# DMB.net
KiCad netlist of a schematic drawn in Altium Designer
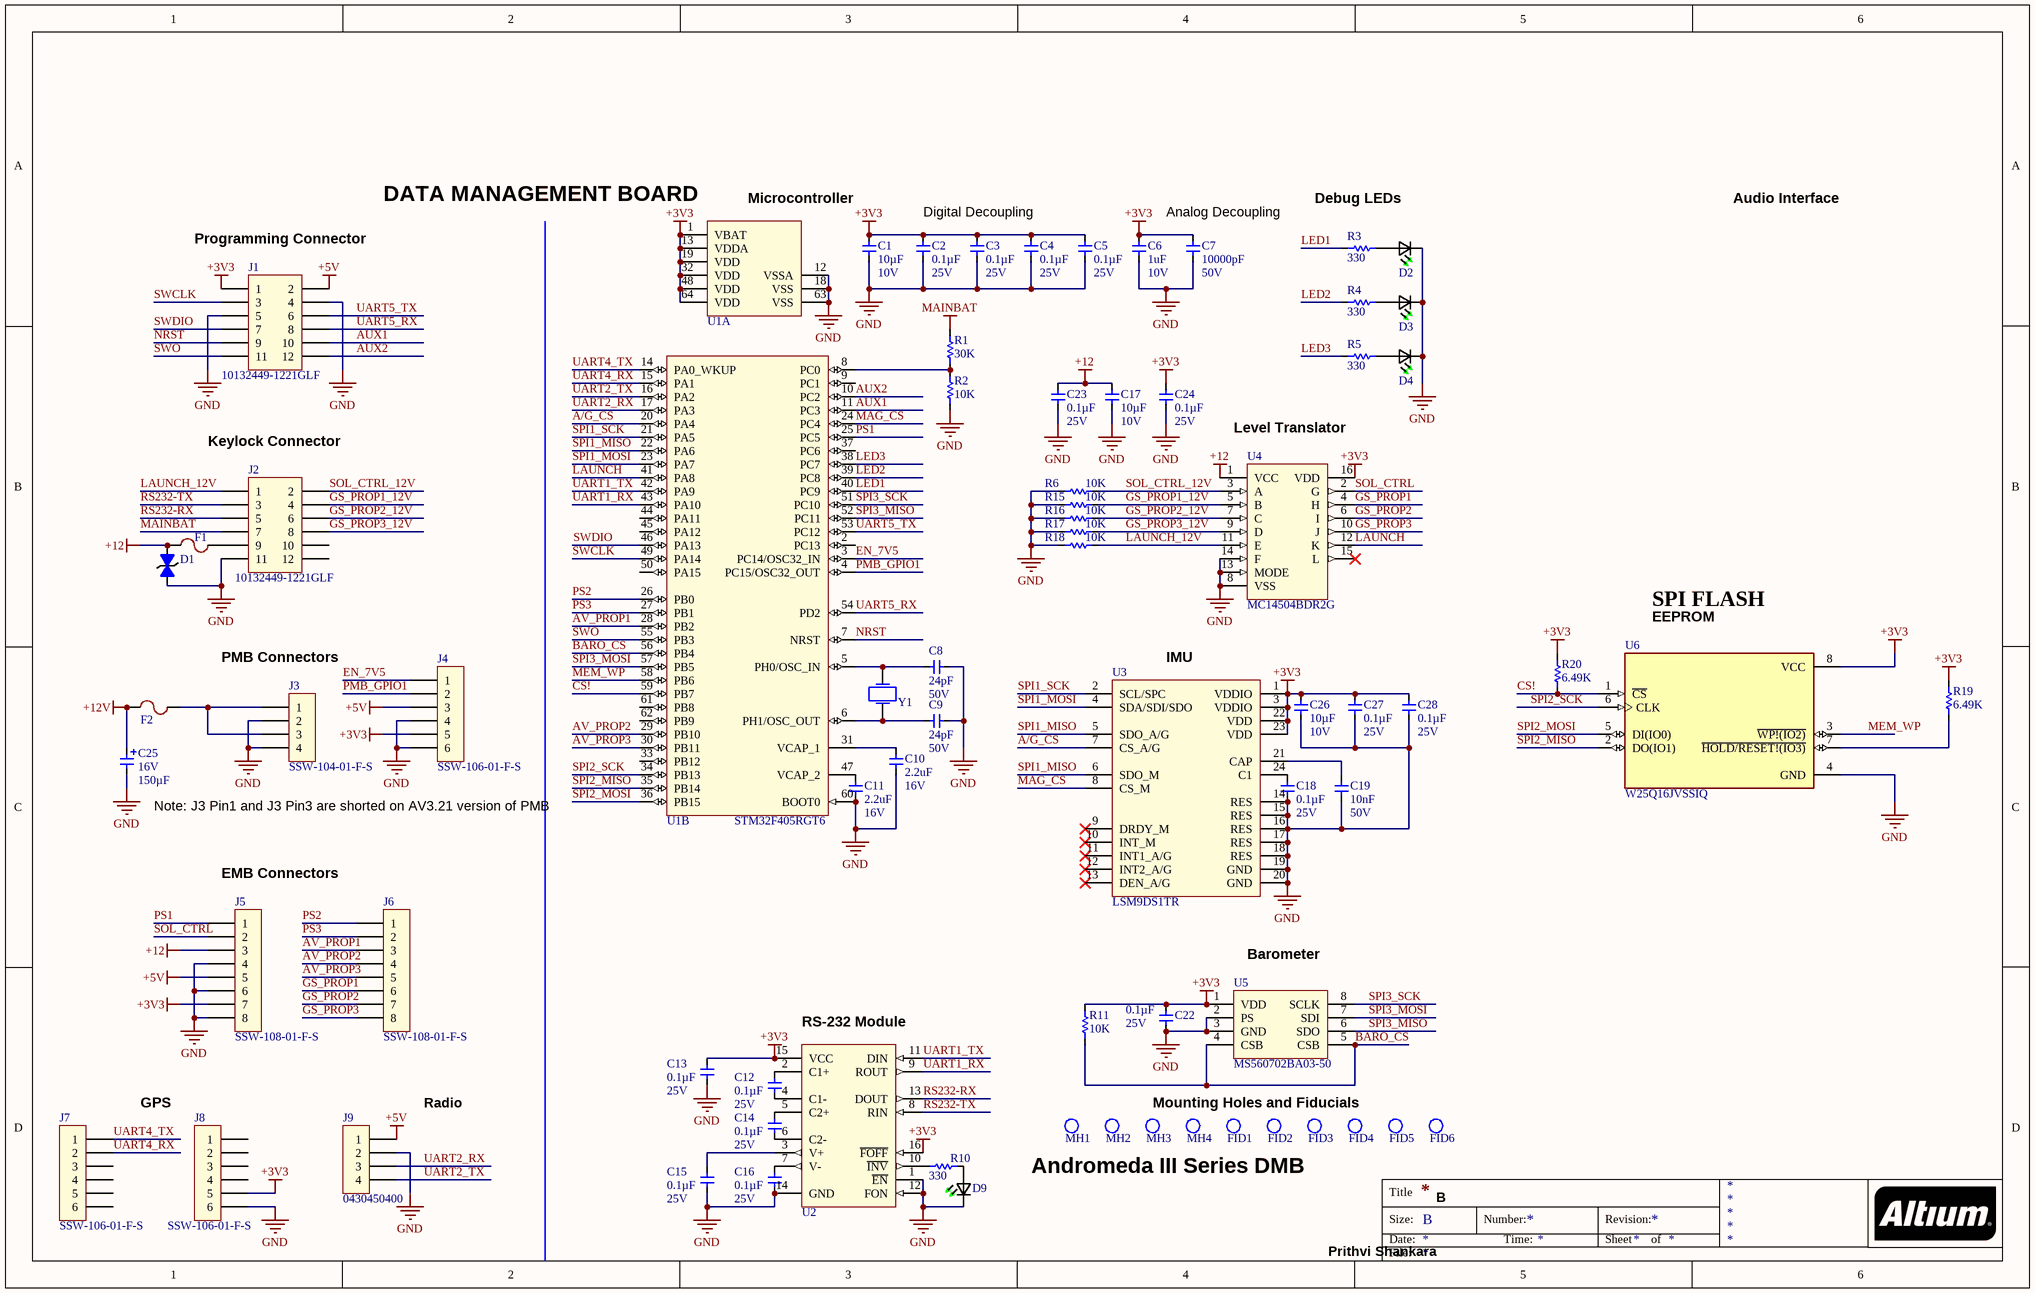
[diagram p0: DMB.SchDoc]

(export (version "E")
  (design (tool "Eeschema 10.0.6"))
  (components
    (comp (ref "C1")
      (value "CL10A106MP8NNNC")
      (footprint "0603[1608]")
      (description "CAP CER 10UF 10V X5R 0603")
      (fields
        (field (name "MANUFACTURER") "Samsung Electro-Mechanics")
        (field (name "TOLERANCE") "±20%")
        (field (name "CAPACITANCE") "10µF")
        (field (name "VOLTAGE - RATED") "10V")
      )
      (libsource (lib "SOARSchematics") (part "CL10A106MP8NNNC"))
    )
    (comp (ref "C2")
      (value "CGA3E2X7R1E104K080AA")
      (footprint "0603[1608]")
      (description "CAP CER 0.1UF 25V X7R 0603")
      (fields
        (field (name "MANUFACTURER") "TDK Corporation")
        (field (name "TOLERANCE") "±10%")
        (field (name "CAPACITANCE") "0.1µF")
        (field (name "VOLTAGE - RATED") "25V")
      )
      (libsource (lib "SOARSchematics") (part "CGA3E2X7R1E104K080AA"))
    )
    (comp (ref "C3")
      (value "CGA3E2X7R1E104K080AA")
      (footprint "0603[1608]")
      (description "CAP CER 0.1UF 25V X7R 0603")
      (fields
        (field (name "MANUFACTURER") "TDK Corporation")
        (field (name "TOLERANCE") "±10%")
        (field (name "CAPACITANCE") "0.1µF")
        (field (name "VOLTAGE - RATED") "25V")
      )
      (libsource (lib "SOARSchematics") (part "CGA3E2X7R1E104K080AA"))
    )
    (comp (ref "C4")
      (value "CGA3E2X7R1E104K080AA")
      (footprint "0603[1608]")
      (description "CAP CER 0.1UF 25V X7R 0603")
      (fields
        (field (name "MANUFACTURER") "TDK Corporation")
        (field (name "TOLERANCE") "±10%")
        (field (name "CAPACITANCE") "0.1µF")
        (field (name "VOLTAGE - RATED") "25V")
      )
      (libsource (lib "SOARSchematics") (part "CGA3E2X7R1E104K080AA"))
    )
    (comp (ref "C5")
      (value "CGA3E2X7R1E104K080AA")
      (footprint "0603[1608]")
      (description "CAP CER 0.1UF 25V X7R 0603")
      (fields
        (field (name "MANUFACTURER") "TDK Corporation")
        (field (name "TOLERANCE") "±10%")
        (field (name "CAPACITANCE") "0.1µF")
        (field (name "VOLTAGE - RATED") "25V")
      )
      (libsource (lib "SOARSchematics") (part "CGA3E2X7R1E104K080AA"))
    )
    (comp (ref "C6")
      (value "CL10A105KP8NNNC")
      (footprint "0603[1608]")
      (description "CAP CER 1UF 10V X5R 0603")
      (fields
        (field (name "MANUFACTURER") "Samsung Electro-Mechanics")
        (field (name "TOLERANCE") "±10%")
        (field (name "CAPACITANCE") "1uF")
        (field (name "VOLTAGE - RATED") "10V")
      )
      (libsource (lib "SOARSchematics") (part "CL10A105KP8NNNC"))
    )
    (comp (ref "C7")
      (value "CGA3E2X7R1H103K080AA")
      (footprint "0603[1608]")
      (description "CAP CER 10000PF 50V X7R 0603")
      (fields
        (field (name "MANUFACTURER") "TDK Corporation")
        (field (name "TOLERANCE") "±10%")
        (field (name "CAPACITANCE") "10000pF")
        (field (name "VOLTAGE - RATED") "50V")
      )
      (libsource (lib "SOARSchematics") (part "CGA3E2X7R1H103K080AA"))
    )
    (comp (ref "C8")
      (value "06035A240JAT2A")
      (footprint "0603[1608]")
      (description "CAP CER 24PF 50V NP0 0603")
      (fields
        (field (name "MANUFACTURER") "AVX Corporation")
        (field (name "TOLERANCE") "±5%")
        (field (name "CAPACITANCE") "24pF")
        (field (name "VOLTAGE - RATED") "50V")
      )
      (libsource (lib "SOARSchematics") (part "06035A240JAT2A"))
    )
    (comp (ref "C9")
      (value "06035A240JAT2A")
      (footprint "0603[1608]")
      (description "CAP CER 24PF 50V NP0 0603")
      (fields
        (field (name "MANUFACTURER") "AVX Corporation")
        (field (name "TOLERANCE") "±5%")
        (field (name "CAPACITANCE") "24pF")
        (field (name "VOLTAGE - RATED") "50V")
      )
      (libsource (lib "SOARSchematics") (part "06035A240JAT2A"))
    )
    (comp (ref "C10")
      (value "C1608X5R1C225K080AB")
      (footprint "0603[1608]")
      (description "CAP CER 2.2UF 16V X5R 0603")
      (fields
        (field (name "MANUFACTURER") "TDK Corporation")
        (field (name "TOLERANCE") "±10%")
        (field (name "CAPACITANCE") "2.2uF")
        (field (name "VOLTAGE - RATED") "16V")
      )
      (libsource (lib "SOARSchematics") (part "C1608X5R1C225K080AB"))
    )
    (comp (ref "C11")
      (value "C1608X5R1C225K080AB")
      (footprint "0603[1608]")
      (description "CAP CER 2.2UF 16V X5R 0603")
      (fields
        (field (name "MANUFACTURER") "TDK Corporation")
        (field (name "TOLERANCE") "±10%")
        (field (name "CAPACITANCE") "2.2uF")
        (field (name "VOLTAGE - RATED") "16V")
      )
      (libsource (lib "SOARSchematics") (part "C1608X5R1C225K080AB"))
    )
    (comp (ref "C12")
      (value "CGA3E2X7R1E104K080AA")
      (footprint "0603[1608]")
      (description "CAP CER 0.1UF 25V X7R 0603")
      (fields
        (field (name "MANUFACTURER") "TDK Corporation")
        (field (name "TOLERANCE") "±10%")
        (field (name "CAPACITANCE") "0.1µF")
        (field (name "VOLTAGE - RATED") "25V")
      )
      (libsource (lib "SOARSchematics") (part "CGA3E2X7R1E104K080AA"))
    )
    (comp (ref "C13")
      (value "CGA3E2X7R1E104K080AA")
      (footprint "0603[1608]")
      (description "CAP CER 0.1UF 25V X7R 0603")
      (fields
        (field (name "MANUFACTURER") "TDK Corporation")
        (field (name "TOLERANCE") "±10%")
        (field (name "CAPACITANCE") "0.1µF")
        (field (name "VOLTAGE - RATED") "25V")
      )
      (libsource (lib "SOARSchematics") (part "CGA3E2X7R1E104K080AA"))
    )
    (comp (ref "C14")
      (value "CGA3E2X7R1E104K080AA")
      (footprint "0603[1608]")
      (description "CAP CER 0.1UF 25V X7R 0603")
      (fields
        (field (name "MANUFACTURER") "TDK Corporation")
        (field (name "TOLERANCE") "±10%")
        (field (name "CAPACITANCE") "0.1µF")
        (field (name "VOLTAGE - RATED") "25V")
      )
      (libsource (lib "SOARSchematics") (part "CGA3E2X7R1E104K080AA"))
    )
    (comp (ref "C15")
      (value "CGA3E2X7R1E104K080AA")
      (footprint "0603[1608]")
      (description "CAP CER 0.1UF 25V X7R 0603")
      (fields
        (field (name "MANUFACTURER") "TDK Corporation")
        (field (name "TOLERANCE") "±10%")
        (field (name "CAPACITANCE") "0.1µF")
        (field (name "VOLTAGE - RATED") "25V")
      )
      (libsource (lib "SOARSchematics") (part "CGA3E2X7R1E104K080AA"))
    )
    (comp (ref "C16")
      (value "CGA3E2X7R1E104K080AA")
      (footprint "0603[1608]")
      (description "CAP CER 0.1UF 25V X7R 0603")
      (fields
        (field (name "MANUFACTURER") "TDK Corporation")
        (field (name "TOLERANCE") "±10%")
        (field (name "CAPACITANCE") "0.1µF")
        (field (name "VOLTAGE - RATED") "25V")
      )
      (libsource (lib "SOARSchematics") (part "CGA3E2X7R1E104K080AA"))
    )
    (comp (ref "C17")
      (value "CL10A106MP8NNNC")
      (footprint "0603[1608]")
      (description "CAP CER 10UF 10V X5R 0603")
      (fields
        (field (name "MANUFACTURER") "Samsung Electro-Mechanics")
        (field (name "TOLERANCE") "±20%")
        (field (name "CAPACITANCE") "10µF")
        (field (name "VOLTAGE - RATED") "10V")
      )
      (libsource (lib "SOARSchematics") (part "CL10A106MP8NNNC"))
    )
    (comp (ref "C18")
      (value "CGA3E2X7R1E104K080AA")
      (footprint "0603[1608]")
      (description "CAP CER 0.1UF 25V X7R 0603")
      (fields
        (field (name "MANUFACTURER") "TDK Corporation")
        (field (name "TOLERANCE") "±10%")
        (field (name "CAPACITANCE") "0.1µF")
        (field (name "VOLTAGE - RATED") "25V")
      )
      (libsource (lib "SOARSchematics") (part "CGA3E2X7R1E104K080AA"))
    )
    (comp (ref "C19")
      (value "GRM1885C1H103JA01D")
      (footprint "0603[1608]")
      (description "CAP CER 10000PF 50V C0G/NP0 0603")
      (fields
        (field (name "MANUFACTURER") "Murata Electronics")
        (field (name "TOLERANCE") "±50%")
        (field (name "CAPACITANCE") "10nF")
        (field (name "VOLTAGE - RATED") "50V")
      )
      (libsource (lib "SOARSchematics") (part "GRM1885C1H103JA01D"))
    )
    (comp (ref "C22")
      (value "CGA3E2X7R1E104K080AA")
      (footprint "0603[1608]")
      (description "CAP CER 0.1UF 25V X7R 0603")
      (fields
        (field (name "MANUFACTURER") "TDK Corporation")
        (field (name "TOLERANCE") "±10%")
        (field (name "CAPACITANCE") "0.1µF")
        (field (name "VOLTAGE - RATED") "25V")
      )
      (libsource (lib "SOARSchematics") (part "CGA3E2X7R1E104K080AA"))
    )
    (comp (ref "C23")
      (value "CGA3E2X7R1E104K080AA")
      (footprint "0603[1608]")
      (description "CAP CER 0.1UF 25V X7R 0603")
      (fields
        (field (name "MANUFACTURER") "TDK Corporation")
        (field (name "TOLERANCE") "±10%")
        (field (name "CAPACITANCE") "0.1µF")
        (field (name "VOLTAGE - RATED") "25V")
      )
      (libsource (lib "SOARSchematics") (part "CGA3E2X7R1E104K080AA"))
    )
    (comp (ref "C24")
      (value "CGA3E2X7R1E104K080AA")
      (footprint "0603[1608]")
      (description "CAP CER 0.1UF 25V X7R 0603")
      (fields
        (field (name "MANUFACTURER") "TDK Corporation")
        (field (name "TOLERANCE") "±10%")
        (field (name "CAPACITANCE") "0.1µF")
        (field (name "VOLTAGE - RATED") "25V")
      )
      (libsource (lib "SOARSchematics") (part "CGA3E2X7R1E104K080AA"))
    )
    (comp (ref "C25")
      (value "TAJD157K016RNJ")
      (footprint "TAJD157K016RNJ")
      (description "CAP TANT 150UF 10% 16V 2917")
      (fields
        (field (name "MANUFACTURER") "AVX Corporation")
        (field (name "TOLERANCE") "±10%")
        (field (name "VOLTAGE - RATED") "16V")
        (field (name "CAPACITANCE") "150µF")
      )
      (libsource (lib "SOARSchematics") (part "TAJD157K016RNJ"))
    )
    (comp (ref "C26")
      (value "CL10A106MP8NNNC")
      (footprint "0603[1608]")
      (description "CAP CER 10UF 10V X5R 0603")
      (fields
        (field (name "MANUFACTURER") "Samsung Electro-Mechanics")
        (field (name "TOLERANCE") "±20%")
        (field (name "CAPACITANCE") "10µF")
        (field (name "VOLTAGE - RATED") "10V")
      )
      (libsource (lib "SOARSchematics") (part "CL10A106MP8NNNC"))
    )
    (comp (ref "C27")
      (value "CGA3E2X7R1E104K080AA")
      (footprint "0603[1608]")
      (description "CAP CER 0.1UF 25V X7R 0603")
      (fields
        (field (name "MANUFACTURER") "TDK Corporation")
        (field (name "TOLERANCE") "±10%")
        (field (name "CAPACITANCE") "0.1µF")
        (field (name "VOLTAGE - RATED") "25V")
      )
      (libsource (lib "SOARSchematics") (part "CGA3E2X7R1E104K080AA"))
    )
    (comp (ref "C28")
      (value "CGA3E2X7R1E104K080AA")
      (footprint "0603[1608]")
      (description "CAP CER 0.1UF 25V X7R 0603")
      (fields
        (field (name "MANUFACTURER") "TDK Corporation")
        (field (name "TOLERANCE") "±10%")
        (field (name "CAPACITANCE") "0.1µF")
        (field (name "VOLTAGE - RATED") "25V")
      )
      (libsource (lib "SOARSchematics") (part "CGA3E2X7R1E104K080AA"))
    )
    (comp (ref "D1")
      (value "CDSOD323-T12C")
      (footprint "CDSOD323-T12C")
      (description "TVS DIODE 12V 28.3V SOD323")
      (fields (field (name "MANUFACTURER") "Bourns Inc."))
      (libsource (lib "SOARSchematics") (part "CDSOD323-T12C"))
    )
    (comp (ref "D2")
      (value "LTST-C191KGKT")
      (footprint "LTST-C191KGKT")
      (description "LED GREEN CLEAR SMD 0603")
      (fields (field (name "MANUFACTURER") "Lite-On Inc."))
      (libsource (lib "SOARSchematics") (part "LTST-C191KGKT"))
    )
    (comp (ref "D3")
      (value "LTST-C191KGKT")
      (footprint "LTST-C191KGKT")
      (description "LED GREEN CLEAR SMD 0603")
      (fields (field (name "MANUFACTURER") "Lite-On Inc."))
      (libsource (lib "SOARSchematics") (part "LTST-C191KGKT"))
    )
    (comp (ref "D4")
      (value "LTST-C191KGKT")
      (footprint "LTST-C191KGKT")
      (description "LED GREEN CLEAR SMD 0603")
      (fields (field (name "MANUFACTURER") "Lite-On Inc."))
      (libsource (lib "SOARSchematics") (part "LTST-C191KGKT"))
    )
    (comp (ref "D9")
      (value "LTST-C191KGKT")
      (footprint "LTST-C191KGKT")
      (description "LED GREEN CLEAR SMD 0603")
      (fields (field (name "MANUFACTURER") "Lite-On Inc."))
      (libsource (lib "SOARSchematics") (part "LTST-C191KGKT"))
    )
    (comp (ref "F1")
      (value "SF-0603FP500M-2")
      (footprint "SF-0603FP500M-2")
      (description "FUSE BOARD MOUNT 5A 32VDC 0603")
      (fields (field (name "MANUFACTURER") "Bourns Inc."))
      (libsource (lib "SOARSchematics") (part "SF-0603FP500M-2"))
    )
    (comp (ref "F2")
      (value "SF-0603FP500M-2")
      (footprint "SF-0603FP500M-2")
      (description "FUSE BOARD MOUNT 5A 32VDC 0603")
      (fields (field (name "MANUFACTURER") "Bourns Inc."))
      (libsource (lib "SOARSchematics") (part "SF-0603FP500M-2"))
    )
    (comp (ref "FID1")
      (value "FID_1MM_ROUND_SL")
      (footprint "FID_1MM_ROUND_SL")
      (description "Fiducial 1mm Round Single Layer")
      (libsource (lib "SOARSchematics") (part "FID_1MM_ROUND_SL"))
    )
    (comp (ref "FID2")
      (value "FID_1MM_ROUND_SL")
      (footprint "FID_1MM_ROUND_SL")
      (description "Fiducial 1mm Round Single Layer")
      (libsource (lib "SOARSchematics") (part "FID_1MM_ROUND_SL"))
    )
    (comp (ref "FID3")
      (value "FID_1MM_ROUND_SL")
      (footprint "FID_1MM_ROUND_SL")
      (description "Fiducial 1mm Round Single Layer")
      (libsource (lib "SOARSchematics") (part "FID_1MM_ROUND_SL"))
    )
    (comp (ref "FID4")
      (value "FID_1MM_ROUND_SL")
      (footprint "FID_1MM_ROUND_SL")
      (description "Fiducial 1mm Round Single Layer")
      (libsource (lib "SOARSchematics") (part "FID_1MM_ROUND_SL"))
    )
    (comp (ref "FID5")
      (value "FID_1MM_ROUND_SL")
      (footprint "FID_1MM_ROUND_SL")
      (description "Fiducial 1mm Round Single Layer")
      (libsource (lib "SOARSchematics") (part "FID_1MM_ROUND_SL"))
    )
    (comp (ref "FID6")
      (value "FID_1MM_ROUND_SL")
      (footprint "FID_1MM_ROUND_SL")
      (description "Fiducial 1mm Round Single Layer")
      (libsource (lib "SOARSchematics") (part "FID_1MM_ROUND_SL"))
    )
    (comp (ref "J1")
      (value "10132449-1221GLF")
      (footprint "10132449-1221GLF")
      (description "CONN HEADER R/A 12POS 3MM")
      (fields (field (name "MANUFACTURER") "Amphenol ICC (FCI)"))
      (libsource (lib "SOARSchematics") (part "10132449-1221GLF"))
    )
    (comp (ref "J2")
      (value "10132449-1221GLF")
      (footprint "10132449-1221GLF")
      (description "CONN HEADER R/A 12POS 3MM")
      (fields (field (name "MANUFACTURER") "Amphenol ICC (FCI)"))
      (libsource (lib "SOARSchematics") (part "10132449-1221GLF"))
    )
    (comp (ref "J3")
      (value "SSW-104-01-F-S")
      (footprint "SSW-104-01-F-S")
      (description "CONN RCPT 4POS FEMALE 0.1 GOLD PCB")
      (fields (field (name "MANUFACTURER") "Samtec Inc."))
      (libsource (lib "SOARSchematics") (part "SSW-104-01-F-S"))
    )
    (comp (ref "J4")
      (value "SSW-106-01-F-S")
      (footprint "SSW-106-01-F-S")
      (description "CONN RCPT 6POS FEMALE 0.1 GOLD PCB")
      (fields (field (name "MANUFACTURER") "Samtec Inc."))
      (libsource (lib "") (part "SSW-106-01-F-S_1"))
    )
    (comp (ref "J5")
      (value "SSW-108-01-F-S")
      (footprint "SSW-108-01-F-S")
      (description "CONN RCPT 8POS FEMALE 0.1 GOLD PCB")
      (fields (field (name "MANUFACTURER") "Samtec Inc."))
      (libsource (lib "SOARSchematics") (part "SSW-108-01-F-S"))
    )
    (comp (ref "J6")
      (value "SSW-108-01-F-S")
      (footprint "SSW-108-01-F-S")
      (description "CONN RCPT 8POS FEMALE 0.1 GOLD PCB")
      (fields (field (name "MANUFACTURER") "Samtec Inc."))
      (libsource (lib "SOARSchematics") (part "SSW-108-01-F-S"))
    )
    (comp (ref "J7")
      (value "SSW-106-01-F-S")
      (footprint "SSW-106-01-F-S")
      (description "CONN RCPT 6POS FEMALE 0.1 GOLD PCB")
      (fields (field (name "MANUFACTURER") "Samtec Inc."))
      (libsource (lib "SOARSchematics") (part "SSW-106-01-F-S"))
    )
    (comp (ref "J8")
      (value "SSW-106-01-F-S")
      (footprint "SSW-106-01-F-S")
      (description "CONN RCPT 6POS FEMALE 0.1 GOLD PCB")
      (fields (field (name "MANUFACTURER") "Samtec Inc."))
      (libsource (lib "SOARSchematics") (part "SSW-106-01-F-S"))
    )
    (comp (ref "J9")
      (value "0430450400")
      (footprint "0430450400")
      (description "CONN HEADER R/A 4POS 3MM")
      (fields (field (name "MANUFACTURER") "Molex"))
      (libsource (lib "SOARSchematics") (part "0430450400"))
    )
    (comp (ref "MH1")
      (value "Mounting Hole")
      (footprint "MOUNT-HOLE")
      (description "#4 Screw, 0.116in Diameter")
      (libsource (lib "SOARSchematics") (part "Mounting Hole"))
    )
    (comp (ref "MH2")
      (value "Mounting Hole")
      (footprint "MOUNT-HOLE")
      (description "#4 Screw, 0.116in Diameter")
      (libsource (lib "SOARSchematics") (part "Mounting Hole"))
    )
    (comp (ref "MH3")
      (value "Mounting Hole")
      (footprint "MOUNT-HOLE")
      (description "#4 Screw, 0.116in Diameter")
      (libsource (lib "SOARSchematics") (part "Mounting Hole"))
    )
    (comp (ref "MH4")
      (value "Mounting Hole")
      (footprint "MOUNT-HOLE")
      (description "#4 Screw, 0.116in Diameter")
      (libsource (lib "SOARSchematics") (part "Mounting Hole"))
    )
    (comp (ref "R1")
      (value "RC0603FR-0730KL")
      (footprint "0603[1608]")
      (description "RES SMD 30K OHM 1% 1/10W 0603")
      (fields
        (field (name "TOLERANCE") "±1%")
        (field (name "MANUFACTURER") "Yageo")
        (field (name "RESISTANCE") "30K")
      )
      (libsource (lib "SOARSchematics") (part "RC0603FR-0730KL"))
    )
    (comp (ref "R2")
      (value "ERJ-3GEYJ103V")
      (footprint "0603[1608]")
      (description "RES SMD 10K OHM 5% 1/10W 0603")
      (fields
        (field (name "TOLERANCE") "±5%")
        (field (name "MANUFACTURER") "Panasonic Electronic Components")
        (field (name "RESISTANCE") "10K")
      )
      (libsource (lib "SOARSchematics") (part "ERJ-3GEYJ103V"))
    )
    (comp (ref "R3")
      (value "RC1608F331CS")
      (footprint "0603[1608]")
      (description "RES SMD 330 OHM 1% 1/10W 0603")
      (fields
        (field (name "TOLERANCE") "±1%")
        (field (name "MANUFACTURER") "Samsung Electro-Mechanics")
        (field (name "RESISTANCE") "330")
      )
      (libsource (lib "SOARSchematics") (part "RC1608F331CS"))
    )
    (comp (ref "R4")
      (value "RC1608F331CS")
      (footprint "0603[1608]")
      (description "RES SMD 330 OHM 1% 1/10W 0603")
      (fields
        (field (name "TOLERANCE") "±1%")
        (field (name "MANUFACTURER") "Samsung Electro-Mechanics")
        (field (name "RESISTANCE") "330")
      )
      (libsource (lib "SOARSchematics") (part "RC1608F331CS"))
    )
    (comp (ref "R5")
      (value "RC1608F331CS")
      (footprint "0603[1608]")
      (description "RES SMD 330 OHM 1% 1/10W 0603")
      (fields
        (field (name "TOLERANCE") "±1%")
        (field (name "MANUFACTURER") "Samsung Electro-Mechanics")
        (field (name "RESISTANCE") "330")
      )
      (libsource (lib "SOARSchematics") (part "RC1608F331CS"))
    )
    (comp (ref "R6")
      (value "ERJ-3GEYJ103V")
      (footprint "0603[1608]")
      (description "RES SMD 10K OHM 5% 1/10W 0603")
      (fields
        (field (name "TOLERANCE") "±5%")
        (field (name "MANUFACTURER") "Panasonic Electronic Components")
        (field (name "RESISTANCE") "10K")
      )
      (libsource (lib "SOARSchematics") (part "ERJ-3GEYJ103V"))
    )
    (comp (ref "R10")
      (value "RC1608F331CS")
      (footprint "0603[1608]")
      (description "RES SMD 330 OHM 1% 1/10W 0603")
      (fields
        (field (name "TOLERANCE") "±1%")
        (field (name "MANUFACTURER") "Samsung Electro-Mechanics")
        (field (name "RESISTANCE") "330")
      )
      (libsource (lib "SOARSchematics") (part "RC1608F331CS"))
    )
    (comp (ref "R11")
      (value "ERJ-3GEYJ103V")
      (footprint "0603[1608]")
      (description "RES SMD 10K OHM 5% 1/10W 0603")
      (fields
        (field (name "TOLERANCE") "±5%")
        (field (name "MANUFACTURER") "Panasonic Electronic Components")
        (field (name "RESISTANCE") "10K")
      )
      (libsource (lib "SOARSchematics") (part "ERJ-3GEYJ103V"))
    )
    (comp (ref "R15")
      (value "ERJ-3GEYJ103V")
      (footprint "0603[1608]")
      (description "RES SMD 10K OHM 5% 1/10W 0603")
      (fields
        (field (name "TOLERANCE") "±5%")
        (field (name "MANUFACTURER") "Panasonic Electronic Components")
        (field (name "RESISTANCE") "10K")
      )
      (libsource (lib "SOARSchematics") (part "ERJ-3GEYJ103V"))
    )
    (comp (ref "R16")
      (value "ERJ-3GEYJ103V")
      (footprint "0603[1608]")
      (description "RES SMD 10K OHM 5% 1/10W 0603")
      (fields
        (field (name "TOLERANCE") "±5%")
        (field (name "MANUFACTURER") "Panasonic Electronic Components")
        (field (name "RESISTANCE") "10K")
      )
      (libsource (lib "SOARSchematics") (part "ERJ-3GEYJ103V"))
    )
    (comp (ref "R17")
      (value "ERJ-3GEYJ103V")
      (footprint "0603[1608]")
      (description "RES SMD 10K OHM 5% 1/10W 0603")
      (fields
        (field (name "TOLERANCE") "±5%")
        (field (name "MANUFACTURER") "Panasonic Electronic Components")
        (field (name "RESISTANCE") "10K")
      )
      (libsource (lib "SOARSchematics") (part "ERJ-3GEYJ103V"))
    )
    (comp (ref "R18")
      (value "ERJ-3GEYJ103V")
      (footprint "0603[1608]")
      (description "RES SMD 10K OHM 5% 1/10W 0603")
      (fields
        (field (name "TOLERANCE") "±5%")
        (field (name "MANUFACTURER") "Panasonic Electronic Components")
        (field (name "RESISTANCE") "10K")
      )
      (libsource (lib "SOARSchematics") (part "ERJ-3GEYJ103V"))
    )
    (comp (ref "R19")
      (value "RT0603DRE076K49L")
      (footprint "0603[1608]")
      (description "RES SMD 6.49KOHM 0.5% 1/10W 0603")
      (fields
        (field (name "TOLERANCE") "±0.5%")
        (field (name "MANUFACTURER") "Yageo")
        (field (name "RESISTANCE") "6.49K")
      )
      (libsource (lib "SOARSchematics") (part "RT0603DRE076K49L"))
    )
    (comp (ref "R20")
      (value "RT0603DRE076K49L")
      (footprint "0603[1608]")
      (description "RES SMD 6.49KOHM 0.5% 1/10W 0603")
      (fields
        (field (name "TOLERANCE") "±0.5%")
        (field (name "MANUFACTURER") "Yageo")
        (field (name "RESISTANCE") "6.49K")
      )
      (libsource (lib "SOARSchematics") (part "RT0603DRE076K49L"))
    )
    (comp (ref "U1")
      (value "STM32F405RGT6")
      (footprint "TSQFP50P1200X1200X160-64N")
      (description "IC MCU 32BIT 1MB FLASH 64LQFP")
      (fields (field (name "MANUFACTURER") "STMicroelectronics"))
      (libsource (lib "SOARSchematics") (part "STM32F405RGT6"))
    )
    (comp (ref "U2")
      (value "MAX3221ECPWR")
      (footprint "SOP65P780X200-16N")
      (description "IC TRANSCEIVER FULL 1/1 16TSSOP")
      (fields (field (name "MANUFACTURER") "Texas Instruments") (field (name "BASE PART NUMBER") "MAX3221E"))
      (libsource (lib "SOARSchematics") (part "MAX3221ECPWR"))
    )
    (comp (ref "U3")
      (value "LSM9DS1TR")
      (footprint "LSM9DS1TR")
      (description "IMU ACCEL/GYRO/MAG I2C/SPI 24LGA")
      (fields (field (name "MANUFACTURER") "STMicroelectronics"))
      (libsource (lib "SOARSchematics") (part "LSM9DS1TR"))
    )
    (comp (ref "U4")
      (value "MC14504BDR2G")
      (footprint "MC14504BDR2G")
      (description "IC TRNSLTR UNIDIRECTIONAL 16SOIC")
      (fields (field (name "MANUFACTURER") "ON Semiconductor"))
      (libsource (lib "SOARSchematics") (part "MC14504BDR2G"))
    )
    (comp (ref "U5")
      (value "MS560702BA03-50")
      (footprint "MS560702BA03-50")
      (description "BAROMETRIC PRESSURE SENSOR")
      (fields
        (field (name "DIGI-KEY PART NUMBER") "223-1198-1-ND")
        (field (name "MANUFACTURER") "TE Connectivity Measurement Specialties")
      )
      (libsource (lib "SOARSchematics") (part "MS560702BA03-50"))
    )
    (comp (ref "U6")
      (value "W25Q16JVSSIQ")
      (footprint "W25Q16JVSSIQ")
      (description "FLASH - NOR Memory IC 16Mb _2M x 8_ SPI - Quad I/O 133MHz 8-SOIC")
      (fields (field (name "MF") "Winbond Electronics"))
      (libsource (lib "SOARSchematics") (part "W25Q16JVSSIQ"))
    )
    (comp (ref "Y1")
      (value "ABLS-8.000MHZ-B2-T")
      (footprint "ABLS-8.000MHZ-B2-T")
      (description "CRYSTAL 8.0000MHZ 18PF SMD")
      (fields (field (name "MANUFACTURER") "Abracon LLC"))
      (libsource (lib "SOARSchematics") (part "ABLS-8.000MHZ-B2-T"))
    )
  )
  (nets
    (net (code "1") (name "+3V3") (class "Default")
      (node (ref "C1") (pin "2") (pinfunction "2_2") (pintype "passive"))
      (node (ref "C13") (pin "2") (pinfunction "2_2") (pintype "passive"))
      (node (ref "C2") (pin "2") (pinfunction "2_2") (pintype "passive"))
      (node (ref "C22") (pin "2") (pinfunction "2_2") (pintype "passive"))
      (node (ref "C24") (pin "2") (pinfunction "2_2") (pintype "passive"))
      (node (ref "C26") (pin "2") (pinfunction "2_2") (pintype "passive"))
      (node (ref "C27") (pin "2") (pinfunction "2_2") (pintype "passive"))
      (node (ref "C28") (pin "2") (pinfunction "2_2") (pintype "passive"))
      (node (ref "C3") (pin "2") (pinfunction "2_2") (pintype "passive"))
      (node (ref "C4") (pin "2") (pinfunction "2_2") (pintype "passive"))
      (node (ref "C5") (pin "2") (pinfunction "2_2") (pintype "passive"))
      (node (ref "C6") (pin "2") (pinfunction "2_2") (pintype "passive"))
      (node (ref "C7") (pin "2") (pinfunction "2_2") (pintype "passive"))
      (node (ref "J1") (pin "1") (pinfunction "1_1") (pintype "passive"))
      (node (ref "J4") (pin "5") (pinfunction "5_5") (pintype "passive"))
      (node (ref "J5") (pin "7") (pinfunction "7_7") (pintype "passive"))
      (node (ref "J8") (pin "5") (pinfunction "5_5") (pintype "passive"))
      (node (ref "R11") (pin "2") (pinfunction "2_2") (pintype "passive"))
      (node (ref "R19") (pin "2") (pinfunction "2_2") (pintype "passive"))
      (node (ref "R20") (pin "2") (pinfunction "2_2") (pintype "passive"))
      (node (ref "U1") (pin "1") (pinfunction "VBAT_1") (pintype "power_in"))
      (node (ref "U1") (pin "13") (pinfunction "VDDA_13") (pintype "power_in"))
      (node (ref "U1") (pin "19") (pinfunction "VDD_19") (pintype "power_in"))
      (node (ref "U1") (pin "32") (pinfunction "VDD_32") (pintype "power_in"))
      (node (ref "U1") (pin "48") (pinfunction "VDD_48") (pintype "power_in"))
      (node (ref "U1") (pin "64") (pinfunction "VDD_64") (pintype "power_in"))
      (node (ref "U2") (pin "15") (pinfunction "VCC_15") (pintype "passive"))
      (node (ref "U2") (pin "16") (pinfunction "~{FOFF}_16") (pintype "input"))
      (node (ref "U3") (pin "1") (pinfunction "VDDIO_1") (pintype "power_in"))
      (node (ref "U3") (pin "22") (pinfunction "VDD_22") (pintype "power_in"))
      (node (ref "U3") (pin "23") (pinfunction "VDD_23") (pintype "power_in"))
      (node (ref "U3") (pin "3") (pinfunction "VDDIO_3") (pintype "power_in"))
      (node (ref "U4") (pin "16") (pinfunction "VDD_16") (pintype "power_in"))
      (node (ref "U5") (pin "1") (pinfunction "VDD_1") (pintype "power_in"))
      (node (ref "U6") (pin "8") (pinfunction "VCC_8") (pintype "power_in"))
    )
    (net (code "2") (name "+5V") (class "Default")
      (node (ref "J1") (pin "2") (pinfunction "2_2") (pintype "passive"))
      (node (ref "J4") (pin "3") (pinfunction "3_3") (pintype "passive"))
      (node (ref "J5") (pin "5") (pinfunction "5_5") (pintype "passive"))
      (node (ref "J9") (pin "1") (pinfunction "1_1") (pintype "passive"))
    )
    (net (code "3") (name "+12") (class "Default")
      (node (ref "C17") (pin "2") (pinfunction "2_2") (pintype "passive"))
      (node (ref "C23") (pin "2") (pinfunction "2_2") (pintype "passive"))
      (node (ref "D1") (pin "1") (pinfunction "1_1") (pintype "power_in"))
      (node (ref "F1") (pin "1") (pinfunction "1_1") (pintype "passive"))
      (node (ref "J5") (pin "3") (pinfunction "3_3") (pintype "passive"))
      (node (ref "U4") (pin "1") (pinfunction "VCC_1") (pintype "power_in"))
    )
    (net (code "4") (name "+12V") (class "Default")
      (node (ref "C25") (pin "1") (pinfunction "1_1") (pintype "passive"))
      (node (ref "F2") (pin "1") (pinfunction "1_1") (pintype "passive"))
    )
    (net (code "6") (name "/AUX1") (class "Default")
      (node (ref "J1") (pin "10") (pinfunction "10_10") (pintype "passive"))
      (node (ref "U1") (pin "11") (pinfunction "PC3_11") (pintype "bidirectional"))
    )
    (net (code "7") (name "/AUX2") (class "Default")
      (node (ref "J1") (pin "12") (pinfunction "12_12") (pintype "passive"))
      (node (ref "U1") (pin "10") (pinfunction "PC2_10") (pintype "bidirectional"))
    )
    (net (code "8") (name "/AV_PROP1") (class "Default")
      (node (ref "J6") (pin "3") (pinfunction "3_3") (pintype "passive"))
      (node (ref "U1") (pin "28") (pinfunction "PB2_28") (pintype "bidirectional"))
    )
    (net (code "9") (name "/AV_PROP2") (class "Default")
      (node (ref "J6") (pin "4") (pinfunction "4_4") (pintype "passive"))
      (node (ref "U1") (pin "29") (pinfunction "PB10_29") (pintype "bidirectional"))
    )
    (net (code "10") (name "/AV_PROP3") (class "Default")
      (node (ref "J6") (pin "5") (pinfunction "5_5") (pintype "passive"))
      (node (ref "U1") (pin "30") (pinfunction "PB11_30") (pintype "bidirectional"))
    )
    (net (code "11") (name "/A{slash}G_~{CS}") (class "Default")
      (node (ref "U1") (pin "20") (pinfunction "PA4_20") (pintype "bidirectional"))
      (node (ref "U3") (pin "7") (pinfunction "CS_A/G_7") (pintype "passive"))
    )
    (net (code "12") (name "/BARO_~{CS}") (class "Default")
      (node (ref "R11") (pin "1") (pinfunction "1_1") (pintype "passive"))
      (node (ref "U1") (pin "56") (pinfunction "PB4_56") (pintype "bidirectional"))
      (node (ref "U5") (pin "4") (pinfunction "CSB_4") (pintype "passive"))
      (node (ref "U5") (pin "5") (pinfunction "CSB_5") (pintype "passive"))
    )
    (net (code "13") (name "/CS!") (class "Default")
      (node (ref "R20") (pin "1") (pinfunction "1_1") (pintype "passive"))
      (node (ref "U1") (pin "59") (pinfunction "PB7_59") (pintype "bidirectional"))
      (node (ref "U6") (pin "1") (pinfunction "~{CS}_1") (pintype "input"))
    )
    (net (code "14") (name "/EN_7V5") (class "Default")
      (node (ref "J4") (pin "1") (pinfunction "1_1") (pintype "passive"))
      (node (ref "U1") (pin "3") (pinfunction "PC14/OSC32_IN_3") (pintype "bidirectional"))
    )
    (net (code "15") (name "/GS_PROP1") (class "Default")
      (node (ref "J6") (pin "6") (pinfunction "6_6") (pintype "passive"))
      (node (ref "U4") (pin "4") (pinfunction "H_4") (pintype "output"))
    )
    (net (code "16") (name "/GS_PROP1_12V") (class "Default")
      (node (ref "J2") (pin "4") (pinfunction "4_4") (pintype "passive"))
      (node (ref "R15") (pin "2") (pinfunction "2_2") (pintype "passive"))
      (node (ref "U4") (pin "5") (pinfunction "B_5") (pintype "input"))
    )
    (net (code "17") (name "/GS_PROP2") (class "Default")
      (node (ref "J6") (pin "7") (pinfunction "7_7") (pintype "passive"))
      (node (ref "U4") (pin "6") (pinfunction "I_6") (pintype "output"))
    )
    (net (code "18") (name "/GS_PROP2_12V") (class "Default")
      (node (ref "J2") (pin "6") (pinfunction "6_6") (pintype "passive"))
      (node (ref "R16") (pin "2") (pinfunction "2_2") (pintype "passive"))
      (node (ref "U4") (pin "7") (pinfunction "C_7") (pintype "input"))
    )
    (net (code "19") (name "/GS_PROP3") (class "Default")
      (node (ref "J6") (pin "8") (pinfunction "8_8") (pintype "passive"))
      (node (ref "U4") (pin "10") (pinfunction "J_10") (pintype "output"))
    )
    (net (code "20") (name "/GS_PROP3_12V") (class "Default")
      (node (ref "J2") (pin "8") (pinfunction "8_8") (pintype "passive"))
      (node (ref "R17") (pin "2") (pinfunction "2_2") (pintype "passive"))
      (node (ref "U4") (pin "9") (pinfunction "D_9") (pintype "input"))
    )
    (net (code "21") (name "/LAUNCH") (class "Default")
      (node (ref "U1") (pin "41") (pinfunction "PA8_41") (pintype "bidirectional"))
      (node (ref "U4") (pin "12") (pinfunction "K_12") (pintype "output"))
    )
    (net (code "22") (name "/LAUNCH_12V") (class "Default")
      (node (ref "J2") (pin "1") (pinfunction "1_1") (pintype "passive"))
      (node (ref "R18") (pin "2") (pinfunction "2_2") (pintype "passive"))
      (node (ref "U4") (pin "11") (pinfunction "E_11") (pintype "input"))
    )
    (net (code "23") (name "/LED1") (class "Default")
      (node (ref "R3") (pin "2") (pinfunction "2_2") (pintype "passive"))
      (node (ref "U1") (pin "40") (pinfunction "PC9_40") (pintype "bidirectional"))
    )
    (net (code "24") (name "/LED2") (class "Default")
      (node (ref "R4") (pin "2") (pinfunction "2_2") (pintype "passive"))
      (node (ref "U1") (pin "39") (pinfunction "PC8_39") (pintype "bidirectional"))
    )
    (net (code "25") (name "/LED3") (class "Default")
      (node (ref "R5") (pin "2") (pinfunction "2_2") (pintype "passive"))
      (node (ref "U1") (pin "38") (pinfunction "PC7_38") (pintype "bidirectional"))
    )
    (net (code "26") (name "/MAG_~{CS}") (class "Default")
      (node (ref "U1") (pin "24") (pinfunction "PC4_24") (pintype "bidirectional"))
      (node (ref "U3") (pin "8") (pinfunction "CS_M_8") (pintype "passive"))
    )
    (net (code "27") (name "/MEM_WP") (class "Default")
      (node (ref "U1") (pin "58") (pinfunction "PB6_58") (pintype "bidirectional"))
      (node (ref "U6") (pin "3") (pinfunction "~{WP!(IO2)}_3") (pintype "bidirectional"))
    )
    (net (code "28") (name "/NRST") (class "Default")
      (node (ref "J1") (pin "9") (pinfunction "9_9") (pintype "passive"))
      (node (ref "U1") (pin "7") (pinfunction "NRST_7") (pintype "bidirectional"))
    )
    (net (code "29") (name "/PMB_GPIO1") (class "Default")
      (node (ref "J4") (pin "2") (pinfunction "2_2") (pintype "passive"))
      (node (ref "U1") (pin "4") (pinfunction "PC15/OSC32_OUT_4") (pintype "bidirectional"))
    )
    (net (code "30") (name "/PS1") (class "Default")
      (node (ref "J5") (pin "1") (pinfunction "1_1") (pintype "passive"))
      (node (ref "U1") (pin "25") (pinfunction "PC5_25") (pintype "bidirectional"))
    )
    (net (code "31") (name "/PS2") (class "Default")
      (node (ref "J6") (pin "1") (pinfunction "1_1") (pintype "passive"))
      (node (ref "U1") (pin "26") (pinfunction "PB0_26") (pintype "bidirectional"))
    )
    (net (code "32") (name "/PS3") (class "Default")
      (node (ref "J6") (pin "2") (pinfunction "2_2") (pintype "passive"))
      (node (ref "U1") (pin "27") (pinfunction "PB1_27") (pintype "bidirectional"))
    )
    (net (code "33") (name "/RS232-RX") (class "Default")
      (node (ref "J2") (pin "5") (pinfunction "5_5") (pintype "passive"))
      (node (ref "U2") (pin "13") (pinfunction "DOUT_13") (pintype "output"))
    )
    (net (code "34") (name "/RS232-TX") (class "Default")
      (node (ref "J2") (pin "3") (pinfunction "3_3") (pintype "passive"))
      (node (ref "U2") (pin "8") (pinfunction "RIN_8") (pintype "input"))
    )
    (net (code "35") (name "/SOL_CTRL") (class "Default")
      (node (ref "J5") (pin "2") (pinfunction "2_2") (pintype "passive"))
      (node (ref "U4") (pin "2") (pinfunction "G_2") (pintype "output"))
    )
    (net (code "36") (name "/SOL_CTRL_12V") (class "Default")
      (node (ref "J2") (pin "2") (pinfunction "2_2") (pintype "passive"))
      (node (ref "R6") (pin "2") (pinfunction "2_2") (pintype "passive"))
      (node (ref "U4") (pin "3") (pinfunction "A_3") (pintype "input"))
    )
    (net (code "37") (name "/SPI1_MISO") (class "Default")
      (node (ref "U1") (pin "22") (pinfunction "PA6_22") (pintype "bidirectional"))
      (node (ref "U3") (pin "5") (pinfunction "SDO_A/G_5") (pintype "passive"))
      (node (ref "U3") (pin "6") (pinfunction "SDO_M_6") (pintype "passive"))
    )
    (net (code "38") (name "/SPI1_MOSI") (class "Default")
      (node (ref "U1") (pin "23") (pinfunction "PA7_23") (pintype "bidirectional"))
      (node (ref "U3") (pin "4") (pinfunction "SDA/SDI/SDO_4") (pintype "passive"))
    )
    (net (code "39") (name "/SPI1_SCK") (class "Default")
      (node (ref "U1") (pin "21") (pinfunction "PA5_21") (pintype "bidirectional"))
      (node (ref "U3") (pin "2") (pinfunction "SCL/SPC_2") (pintype "passive"))
    )
    (net (code "40") (name "/SPI2_MISO") (class "Default")
      (node (ref "U1") (pin "35") (pinfunction "PB14_35") (pintype "bidirectional"))
      (node (ref "U6") (pin "2") (pinfunction "DO(IO1)_2") (pintype "bidirectional"))
    )
    (net (code "41") (name "/SPI2_MOSI") (class "Default")
      (node (ref "U1") (pin "36") (pinfunction "PB15_36") (pintype "bidirectional"))
      (node (ref "U6") (pin "5") (pinfunction "DI(IO0)_5") (pintype "bidirectional"))
    )
    (net (code "42") (name "/SPI2_SCK") (class "Default")
      (node (ref "U1") (pin "34") (pinfunction "PB13_34") (pintype "bidirectional"))
      (node (ref "U6") (pin "6") (pinfunction "CLK_6") (pintype "input"))
    )
    (net (code "43") (name "/SPI3_MISO") (class "Default")
      (node (ref "U1") (pin "52") (pinfunction "PC11_52") (pintype "bidirectional"))
      (node (ref "U5") (pin "6") (pinfunction "SDO_6") (pintype "passive"))
    )
    (net (code "44") (name "/SPI3_MOSI") (class "Default")
      (node (ref "U1") (pin "57") (pinfunction "PB5_57") (pintype "bidirectional"))
      (node (ref "U5") (pin "7") (pinfunction "SDI_7") (pintype "passive"))
    )
    (net (code "45") (name "/SPI3_SCK") (class "Default")
      (node (ref "U1") (pin "51") (pinfunction "PC10_51") (pintype "bidirectional"))
      (node (ref "U5") (pin "8") (pinfunction "SCLK_8") (pintype "passive"))
    )
    (net (code "46") (name "/SWCLK") (class "Default")
      (node (ref "J1") (pin "3") (pinfunction "3_3") (pintype "passive"))
      (node (ref "U1") (pin "49") (pinfunction "PA14_49") (pintype "bidirectional"))
    )
    (net (code "47") (name "/SWDIO") (class "Default")
      (node (ref "J1") (pin "7") (pinfunction "7_7") (pintype "passive"))
      (node (ref "U1") (pin "46") (pinfunction "PA13_46") (pintype "bidirectional"))
    )
    (net (code "48") (name "/SWO") (class "Default")
      (node (ref "J1") (pin "11") (pinfunction "11_11") (pintype "passive"))
      (node (ref "U1") (pin "55") (pinfunction "PB3_55") (pintype "bidirectional"))
    )
    (net (code "49") (name "/UART1_RX") (class "Default")
      (node (ref "U1") (pin "43") (pinfunction "PA10_43") (pintype "bidirectional"))
      (node (ref "U2") (pin "9") (pinfunction "ROUT_9") (pintype "output"))
    )
    (net (code "50") (name "/UART1_TX") (class "Default")
      (node (ref "U1") (pin "42") (pinfunction "PA9_42") (pintype "bidirectional"))
      (node (ref "U2") (pin "11") (pinfunction "DIN_11") (pintype "input"))
    )
    (net (code "51") (name "/UART2_RX") (class "Default")
      (node (ref "J9") (pin "3") (pinfunction "3_3") (pintype "passive"))
      (node (ref "U1") (pin "17") (pinfunction "PA3_17") (pintype "bidirectional"))
    )
    (net (code "52") (name "/UART2_TX") (class "Default")
      (node (ref "J9") (pin "4") (pinfunction "4_4") (pintype "passive"))
      (node (ref "U1") (pin "16") (pinfunction "PA2_16") (pintype "bidirectional"))
    )
    (net (code "53") (name "/UART4_RX") (class "Default")
      (node (ref "J7") (pin "2") (pinfunction "2_2") (pintype "passive"))
      (node (ref "U1") (pin "15") (pinfunction "PA1_15") (pintype "bidirectional"))
    )
    (net (code "54") (name "/UART4_TX") (class "Default")
      (node (ref "J7") (pin "1") (pinfunction "1_1") (pintype "passive"))
      (node (ref "U1") (pin "14") (pinfunction "PA0_WKUP_14") (pintype "bidirectional"))
    )
    (net (code "55") (name "/UART5_RX") (class "Default")
      (node (ref "J1") (pin "8") (pinfunction "8_8") (pintype "passive"))
      (node (ref "U1") (pin "54") (pinfunction "PD2_54") (pintype "bidirectional"))
    )
    (net (code "56") (name "/UART5_TX") (class "Default")
      (node (ref "J1") (pin "6") (pinfunction "6_6") (pintype "passive"))
      (node (ref "U1") (pin "53") (pinfunction "PC12_53") (pintype "bidirectional"))
    )
    (net (code "57") (name "GND") (class "Default")
      (node (ref "C1") (pin "1") (pinfunction "1_1") (pintype "passive"))
      (node (ref "C10") (pin "1") (pinfunction "1_1") (pintype "passive"))
      (node (ref "C11") (pin "1") (pinfunction "1_1") (pintype "passive"))
      (node (ref "C13") (pin "1") (pinfunction "1_1") (pintype "passive"))
      (node (ref "C15") (pin "1") (pinfunction "1_1") (pintype "passive"))
      (node (ref "C16") (pin "1") (pinfunction "1_1") (pintype "passive"))
      (node (ref "C17") (pin "1") (pinfunction "1_1") (pintype "passive"))
      (node (ref "C18") (pin "1") (pinfunction "1_1") (pintype "passive"))
      (node (ref "C19") (pin "1") (pinfunction "1_1") (pintype "passive"))
      (node (ref "C2") (pin "1") (pinfunction "1_1") (pintype "passive"))
      (node (ref "C22") (pin "1") (pinfunction "1_1") (pintype "passive"))
      (node (ref "C23") (pin "1") (pinfunction "1_1") (pintype "passive"))
      (node (ref "C24") (pin "1") (pinfunction "1_1") (pintype "passive"))
      (node (ref "C25") (pin "2") (pinfunction "2_2") (pintype "passive"))
      (node (ref "C26") (pin "1") (pinfunction "1_1") (pintype "passive"))
      (node (ref "C27") (pin "1") (pinfunction "1_1") (pintype "passive"))
      (node (ref "C28") (pin "1") (pinfunction "1_1") (pintype "passive"))
      (node (ref "C3") (pin "1") (pinfunction "1_1") (pintype "passive"))
      (node (ref "C4") (pin "1") (pinfunction "1_1") (pintype "passive"))
      (node (ref "C5") (pin "1") (pinfunction "1_1") (pintype "passive"))
      (node (ref "C6") (pin "1") (pinfunction "1_1") (pintype "passive"))
      (node (ref "C7") (pin "1") (pinfunction "1_1") (pintype "passive"))
      (node (ref "C8") (pin "2") (pinfunction "2_2") (pintype "passive"))
      (node (ref "C9") (pin "2") (pinfunction "2_2") (pintype "passive"))
      (node (ref "D1") (pin "2") (pinfunction "2_2") (pintype "power_in"))
      (node (ref "D2") (pin "1") (pinfunction "K2_1") (pintype "passive"))
      (node (ref "D3") (pin "1") (pinfunction "K2_1") (pintype "passive"))
      (node (ref "D4") (pin "1") (pinfunction "K2_1") (pintype "passive"))
      (node (ref "D9") (pin "1") (pinfunction "K2_1") (pintype "passive"))
      (node (ref "J1") (pin "4") (pinfunction "4_4") (pintype "passive"))
      (node (ref "J1") (pin "5") (pinfunction "5_5") (pintype "passive"))
      (node (ref "J2") (pin "11") (pinfunction "11_11") (pintype "passive"))
      (node (ref "J3") (pin "2") (pinfunction "2_2") (pintype "passive"))
      (node (ref "J3") (pin "4") (pinfunction "4_4") (pintype "passive"))
      (node (ref "J4") (pin "4") (pinfunction "4_4") (pintype "passive"))
      (node (ref "J4") (pin "6") (pinfunction "6_6") (pintype "passive"))
      (node (ref "J5") (pin "4") (pinfunction "4_4") (pintype "passive"))
      (node (ref "J5") (pin "6") (pinfunction "6_6") (pintype "passive"))
      (node (ref "J5") (pin "8") (pinfunction "8_8") (pintype "passive"))
      (node (ref "J8") (pin "6") (pinfunction "6_6") (pintype "passive"))
      (node (ref "J9") (pin "2") (pinfunction "2_2") (pintype "passive"))
      (node (ref "R15") (pin "1") (pinfunction "1_1") (pintype "passive"))
      (node (ref "R16") (pin "1") (pinfunction "1_1") (pintype "passive"))
      (node (ref "R17") (pin "1") (pinfunction "1_1") (pintype "passive"))
      (node (ref "R18") (pin "1") (pinfunction "1_1") (pintype "passive"))
      (node (ref "R2") (pin "1") (pinfunction "1_1") (pintype "passive"))
      (node (ref "R6") (pin "1") (pinfunction "1_1") (pintype "passive"))
      (node (ref "U1") (pin "12") (pinfunction "VSSA_12") (pintype "power_in"))
      (node (ref "U1") (pin "18") (pinfunction "VSS_18") (pintype "power_in"))
      (node (ref "U1") (pin "60") (pinfunction "BOOT0_60") (pintype "input"))
      (node (ref "U1") (pin "63") (pinfunction "VSS_63") (pintype "power_in"))
      (node (ref "U2") (pin "1") (pinfunction "~{EN}_1") (pintype "passive"))
      (node (ref "U2") (pin "12") (pinfunction "FON_12") (pintype "input"))
      (node (ref "U2") (pin "14") (pinfunction "GND_14") (pintype "passive"))
      (node (ref "U3") (pin "14") (pinfunction "RES_14") (pintype "passive"))
      (node (ref "U3") (pin "15") (pinfunction "RES_15") (pintype "passive"))
      (node (ref "U3") (pin "16") (pinfunction "RES_16") (pintype "passive"))
      (node (ref "U3") (pin "17") (pinfunction "RES_17") (pintype "passive"))
      (node (ref "U3") (pin "18") (pinfunction "RES_18") (pintype "passive"))
      (node (ref "U3") (pin "19") (pinfunction "GND_19") (pintype "power_in"))
      (node (ref "U3") (pin "20") (pinfunction "GND_20") (pintype "power_in"))
      (node (ref "U4") (pin "13") (pinfunction "MODE_13") (pintype "input"))
      (node (ref "U4") (pin "14") (pinfunction "F_14") (pintype "input"))
      (node (ref "U4") (pin "8") (pinfunction "VSS_8") (pintype "power_in"))
      (node (ref "U5") (pin "2") (pinfunction "PS_2") (pintype "passive"))
      (node (ref "U5") (pin "3") (pinfunction "GND_3") (pintype "passive"))
      (node (ref "U6") (pin "4") (pinfunction "GND_4") (pintype "power_in"))
    )
    (net (code "58") (name "MAINBAT") (class "Default")
      (node (ref "J2") (pin "7") (pinfunction "7_7") (pintype "passive"))
      (node (ref "R1") (pin "2") (pinfunction "2_2") (pintype "passive"))
    )
    (net (code "59") (name "Net-(D2-A2)") (class "Default")
      (node (ref "D2") (pin "2") (pinfunction "A2_2") (pintype "passive"))
      (node (ref "R3") (pin "1") (pinfunction "1_1") (pintype "passive"))
    )
    (net (code "60") (name "Net-(D3-A2)") (class "Default")
      (node (ref "D3") (pin "2") (pinfunction "A2_2") (pintype "passive"))
      (node (ref "R4") (pin "1") (pinfunction "1_1") (pintype "passive"))
    )
    (net (code "61") (name "Net-(D4-A2)") (class "Default")
      (node (ref "D4") (pin "2") (pinfunction "A2_2") (pintype "passive"))
      (node (ref "R5") (pin "1") (pinfunction "1_1") (pintype "passive"))
    )
    (net (code "62") (name "Net-(D9-A2)") (class "Default")
      (node (ref "D9") (pin "2") (pinfunction "A2_2") (pintype "passive"))
      (node (ref "R10") (pin "2") (pinfunction "2_2") (pintype "passive"))
    )
    (net (code "63") (name "Net-(F1-Pad2)") (class "Default")
      (node (ref "F1") (pin "2") (pinfunction "2_2") (pintype "passive"))
      (node (ref "J2") (pin "9") (pinfunction "9_9") (pintype "passive"))
    )
    (net (code "64") (name "Net-(F2-Pad2)") (class "Default")
      (node (ref "F2") (pin "2") (pinfunction "2_2") (pintype "passive"))
      (node (ref "J3") (pin "1") (pinfunction "1_1") (pintype "passive"))
      (node (ref "J3") (pin "3") (pinfunction "3_3") (pintype "passive"))
    )
    (net (code "65") (name "Net-(U1B-PC0)") (class "Default")
      (node (ref "R1") (pin "1") (pinfunction "1_1") (pintype "passive"))
      (node (ref "R2") (pin "2") (pinfunction "2_2") (pintype "passive"))
      (node (ref "U1") (pin "8") (pinfunction "PC0_8") (pintype "bidirectional"))
    )
    (net (code "66") (name "Net-(U1B-PH0{slash}OSC_IN)") (class "Default")
      (node (ref "C8") (pin "1") (pinfunction "1_1") (pintype "passive"))
      (node (ref "U1") (pin "5") (pinfunction "PH0/OSC_IN_5") (pintype "bidirectional"))
      (node (ref "Y1") (pin "2") (pinfunction "2_2") (pintype "power_in"))
    )
    (net (code "67") (name "Net-(U1B-PH1{slash}OSC_OUT)") (class "Default")
      (node (ref "C9") (pin "1") (pinfunction "1_1") (pintype "passive"))
      (node (ref "U1") (pin "6") (pinfunction "PH1/OSC_OUT_6") (pintype "bidirectional"))
      (node (ref "Y1") (pin "1") (pinfunction "1_1") (pintype "power_in"))
    )
    (net (code "68") (name "Net-(U1B-VCAP_1)") (class "Default")
      (node (ref "C10") (pin "2") (pinfunction "2_2") (pintype "passive"))
      (node (ref "U1") (pin "31") (pinfunction "VCAP_1_31") (pintype "power_in"))
    )
    (net (code "69") (name "Net-(U1B-VCAP_2)") (class "Default")
      (node (ref "C11") (pin "2") (pinfunction "2_2") (pintype "passive"))
      (node (ref "U1") (pin "47") (pinfunction "VCAP_2_47") (pintype "power_in"))
    )
    (net (code "70") (name "Net-(U2-C1+)") (class "Default")
      (node (ref "C12") (pin "2") (pinfunction "2_2") (pintype "passive"))
      (node (ref "U2") (pin "2") (pinfunction "C1+_2") (pintype "passive"))
    )
    (net (code "71") (name "Net-(U2-C1-)") (class "Default")
      (node (ref "C12") (pin "1") (pinfunction "1_1") (pintype "passive"))
      (node (ref "U2") (pin "4") (pinfunction "C1-_4") (pintype "passive"))
    )
    (net (code "72") (name "Net-(U2-C2+)") (class "Default")
      (node (ref "C14") (pin "2") (pinfunction "2_2") (pintype "passive"))
      (node (ref "U2") (pin "5") (pinfunction "C2+_5") (pintype "passive"))
    )
    (net (code "73") (name "Net-(U2-C2-)") (class "Default")
      (node (ref "C14") (pin "1") (pinfunction "1_1") (pintype "passive"))
      (node (ref "U2") (pin "6") (pinfunction "C2-_6") (pintype "passive"))
    )
    (net (code "74") (name "Net-(U2-V+)") (class "Default")
      (node (ref "C15") (pin "2") (pinfunction "2_2") (pintype "passive"))
      (node (ref "U2") (pin "3") (pinfunction "V+_3") (pintype "output"))
    )
    (net (code "75") (name "Net-(U2-V-)") (class "Default")
      (node (ref "C16") (pin "2") (pinfunction "2_2") (pintype "passive"))
      (node (ref "U2") (pin "7") (pinfunction "V-_7") (pintype "output"))
    )
    (net (code "76") (name "Net-(U2-~{INV})") (class "Default")
      (node (ref "R10") (pin "1") (pinfunction "1_1") (pintype "passive"))
      (node (ref "U2") (pin "10") (pinfunction "~{INV}_10") (pintype "output"))
    )
    (net (code "77") (name "Net-(U3-C1)") (class "Default")
      (node (ref "C18") (pin "2") (pinfunction "2_2") (pintype "passive"))
      (node (ref "U3") (pin "24") (pinfunction "C1_24") (pintype "passive"))
    )
    (net (code "78") (name "Net-(U3-CAP)") (class "Default")
      (node (ref "C19") (pin "2") (pinfunction "2_2") (pintype "passive"))
      (node (ref "U3") (pin "21") (pinfunction "CAP_21") (pintype "passive"))
    )
    (net (code "79") (name "Net-(U6-~{HOLD{slash}RESET!(IO3)})") (class "Default")
      (node (ref "R19") (pin "1") (pinfunction "1_1") (pintype "passive"))
      (node (ref "U6") (pin "7") (pinfunction "~{HOLD/RESET!(IO3)}_7") (pintype "bidirectional"))
    )
    (net (code "80") (name "unconnected-(J2-Pad10)") (class "Default")
      (node (ref "J2") (pin "10") (pinfunction "10_10") (pintype "passive"))
    )
    (net (code "81") (name "unconnected-(J2-Pad12)") (class "Default")
      (node (ref "J2") (pin "12") (pinfunction "12_12") (pintype "passive"))
    )
    (net (code "82") (name "unconnected-(J7-Pad3)") (class "Default")
      (node (ref "J7") (pin "3") (pinfunction "3_3") (pintype "passive"))
    )
    (net (code "83") (name "unconnected-(J7-Pad4)") (class "Default")
      (node (ref "J7") (pin "4") (pinfunction "4_4") (pintype "passive"))
    )
    (net (code "84") (name "unconnected-(J7-Pad5)") (class "Default")
      (node (ref "J7") (pin "5") (pinfunction "5_5") (pintype "passive"))
    )
    (net (code "85") (name "unconnected-(J7-Pad6)") (class "Default")
      (node (ref "J7") (pin "6") (pinfunction "6_6") (pintype "passive"))
    )
    (net (code "86") (name "unconnected-(J8-Pad1)") (class "Default")
      (node (ref "J8") (pin "1") (pinfunction "1_1") (pintype "passive"))
    )
    (net (code "87") (name "unconnected-(J8-Pad2)") (class "Default")
      (node (ref "J8") (pin "2") (pinfunction "2_2") (pintype "passive"))
    )
    (net (code "88") (name "unconnected-(J8-Pad3)") (class "Default")
      (node (ref "J8") (pin "3") (pinfunction "3_3") (pintype "passive"))
    )
    (net (code "89") (name "unconnected-(J8-Pad4)") (class "Default")
      (node (ref "J8") (pin "4") (pinfunction "4_4") (pintype "passive"))
    )
    (net (code "90") (name "unconnected-(U1B-PA11-Pad44)") (class "Default")
      (node (ref "U1") (pin "44") (pinfunction "PA11_44") (pintype "bidirectional"))
    )
    (net (code "91") (name "unconnected-(U1B-PA12-Pad45)") (class "Default")
      (node (ref "U1") (pin "45") (pinfunction "PA12_45") (pintype "bidirectional"))
    )
    (net (code "92") (name "unconnected-(U1B-PA15-Pad50)") (class "Default")
      (node (ref "U1") (pin "50") (pinfunction "PA15_50") (pintype "bidirectional"))
    )
    (net (code "93") (name "unconnected-(U1B-PB8-Pad61)") (class "Default")
      (node (ref "U1") (pin "61") (pinfunction "PB8_61") (pintype "bidirectional"))
    )
    (net (code "94") (name "unconnected-(U1B-PB9-Pad62)") (class "Default")
      (node (ref "U1") (pin "62") (pinfunction "PB9_62") (pintype "bidirectional"))
    )
    (net (code "95") (name "unconnected-(U1B-PB12-Pad33)") (class "Default")
      (node (ref "U1") (pin "33") (pinfunction "PB12_33") (pintype "bidirectional"))
    )
    (net (code "96") (name "unconnected-(U1B-PC1-Pad9)") (class "Default")
      (node (ref "U1") (pin "9") (pinfunction "PC1_9") (pintype "bidirectional"))
    )
    (net (code "97") (name "unconnected-(U1B-PC6-Pad37)") (class "Default")
      (node (ref "U1") (pin "37") (pinfunction "PC6_37") (pintype "bidirectional"))
    )
    (net (code "98") (name "unconnected-(U1B-PC13-Pad2)") (class "Default")
      (node (ref "U1") (pin "2") (pinfunction "PC13_2") (pintype "bidirectional"))
    )
    (net (code "99") (name "unconnected-(U3-DEN_A{slash}G-Pad13)") (class "Default")
      (node (ref "U3") (pin "13") (pinfunction "DEN_A/G_13") (pintype "passive+no_connect"))
    )
    (net (code "100") (name "unconnected-(U3-DRDY_M-Pad9)") (class "Default")
      (node (ref "U3") (pin "9") (pinfunction "DRDY_M_9") (pintype "passive+no_connect"))
    )
    (net (code "101") (name "unconnected-(U3-INT1_A{slash}G-Pad11)") (class "Default")
      (node (ref "U3") (pin "11") (pinfunction "INT1_A/G_11") (pintype "passive+no_connect"))
    )
    (net (code "102") (name "unconnected-(U3-INT2_A{slash}G-Pad12)") (class "Default")
      (node (ref "U3") (pin "12") (pinfunction "INT2_A/G_12") (pintype "passive+no_connect"))
    )
    (net (code "103") (name "unconnected-(U3-INT_M-Pad10)") (class "Default")
      (node (ref "U3") (pin "10") (pinfunction "INT_M_10") (pintype "passive+no_connect"))
    )
    (net (code "104") (name "unconnected-(U4-L-Pad15)") (class "Default")
      (node (ref "U4") (pin "15") (pinfunction "L_15") (pintype "output+no_connect"))
    )
  )
)
